# PowerSupply.net
KiCad netlist of a schematic drawn in Altium Designer
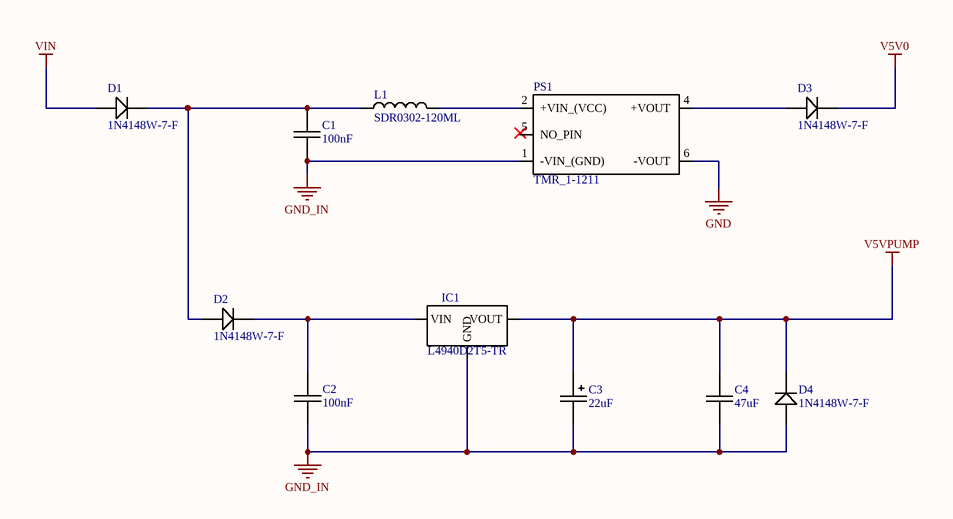
[diagram p0: PowerSupply.SchDoc]

(export (version "E")
  (design (tool "Eeschema 10.0.6"))
  (components
    (comp (ref "C1")
      (value "100nF")
      (footprint "SMD-CAP_1206_IPC_M")
      (description "Capacitor")
      (fields
        (field (name "MOUSER2 PART NUMBER") "80-C1206C104J3J")
        (field (name "MANUFACTURER_PART_NUMBER") "C1206C104J3JACTU")
      )
      (libsource (lib "JMD_Parts") (part "CAP-100NF-1206-5%-25V"))
    )
    (comp (ref "C2")
      (value "100nF")
      (footprint "SMD-CAP_1206_IPC_M")
      (description "Capacitor")
      (fields
        (field (name "MOUSER2 PART NUMBER") "80-C1206C104J3J")
        (field (name "MANUFACTURER_PART_NUMBER") "C1206C104J3JACTU")
      )
      (libsource (lib "JMD_Parts") (part "CAP-100NF-1206-5%-25V"))
    )
    (comp (ref "C3")
      (value "22uF")
      (footprint "CAPPM3216X180N")
      (description "Capacitor Polarised")
      (fields
        (field (name "MOUSER2 PART NUMBER") "581-TPSA226K010T0900")
        (field (name "MANUFACTURER_PART_NUMBER") "TPSA226K010T0900")
      )
      (libsource (lib "JMD_Parts") (part "CAP-22uF-Tantal-10%-10V"))
    )
    (comp (ref "C4")
      (value "47uF")
      (footprint "CAPC3216X180N")
      (description "Capacitor")
      (fields
        (field (name "MOUSER2 PART NUMBER") "80-C1206C476M8P")
        (field (name "MANUFACTURER_PART_NUMBER") "C1206C476M8PACTU")
      )
      (libsource (lib "JMD_Parts") (part "CAP-47UF-1206-20%-10V"))
    )
    (comp (ref "D1")
      (value "1N4148W-7-F")
      (footprint "SOD3716X115N")
      (description "Diode")
      (fields (field (name "MOUSER2 PART NUMBER") "621-1N4148W-F"))
      (libsource (lib "JMD_Parts") (part "1N4148W-7-F"))
    )
    (comp (ref "D2")
      (value "1N4148W-7-F")
      (footprint "SOD3716X115N")
      (description "Diode")
      (fields (field (name "MOUSER2 PART NUMBER") "621-1N4148W-F"))
      (libsource (lib "JMD_Parts") (part "1N4148W-7-F"))
    )
    (comp (ref "D3")
      (value "1N4148W-7-F")
      (footprint "SOD3716X115N")
      (description "Diode")
      (fields (field (name "MOUSER2 PART NUMBER") "621-1N4148W-F"))
      (libsource (lib "JMD_Parts") (part "1N4148W-7-F"))
    )
    (comp (ref "D4")
      (value "1N4148W-7-F")
      (footprint "SOD3716X115N")
      (description "Diode")
      (fields (field (name "MOUSER2 PART NUMBER") "621-1N4148W-F"))
      (libsource (lib "JMD_Parts") (part "1N4148W-7-F"))
    )
    (comp (ref "IC1")
      (value "L4940D2T5-TR")
      (footprint "ST_D2PAK")
      (description "Integrated Circuit")
      (libsource (lib "JMD_Parts") (part "L4940D2T5-TR"))
    )
    (comp (ref "L1")
      (value "SDR0302-120ML")
      (footprint "SDR0302-471KL")
      (description "Inductor")
      (fields (field (name "MOUSER2 PART NUMBER") "652-SDR0302-120ML"))
      (libsource (lib "JMD_Parts") (part "SDR0302-120ML"))
    )
    (comp (ref "PS1")
      (value "TMR_1-1211")
      (footprint "TMR-1-1215")
      (description "Power Supply")
      (fields
        (field (name "MOUSER2 PART NUMBER") "495-TMR-1-1211")
        (field (name "MANUFACTURER_PART_NUMBER") "TMR 1-1211")
      )
      (libsource (lib "JMD_Parts") (part "TMR_1-1211"))
    )
  )
  (nets
    (net (code "1") (name "GND") (class "Default")
      (node (ref "PS1") (pin "6") (pinfunction "-VOUT_6") (pintype "passive"))
    )
    (net (code "2") (name "GND_IN") (class "Default")
      (node (ref "C1") (pin "1") (pinfunction "1_1") (pintype "passive"))
      (node (ref "C2") (pin "1") (pinfunction "1_1") (pintype "passive"))
      (node (ref "C3") (pin "2") (pinfunction "2_2") (pintype "passive"))
      (node (ref "C4") (pin "1") (pinfunction "1_1") (pintype "passive"))
      (node (ref "D4") (pin "2") (pinfunction "A_2") (pintype "passive"))
      (node (ref "IC1") (pin "3") (pinfunction "GND_3") (pintype "passive"))
      (node (ref "PS1") (pin "1") (pinfunction "-VIN_(GND)_1") (pintype "passive"))
    )
    (net (code "3") (name "Net-(D1-K)") (class "Default")
      (node (ref "C1") (pin "2") (pinfunction "2_2") (pintype "passive"))
      (node (ref "D1") (pin "1") (pinfunction "K_1") (pintype "passive"))
      (node (ref "D2") (pin "2") (pinfunction "A_2") (pintype "passive"))
      (node (ref "L1") (pin "1") (pintype "passive"))
    )
    (net (code "4") (name "Net-(D2-K)") (class "Default")
      (node (ref "C2") (pin "2") (pinfunction "2_2") (pintype "passive"))
      (node (ref "D2") (pin "1") (pinfunction "K_1") (pintype "passive"))
      (node (ref "IC1") (pin "1") (pinfunction "VIN_1") (pintype "passive"))
    )
    (net (code "5") (name "Net-(D3-A)") (class "Default")
      (node (ref "D3") (pin "2") (pinfunction "A_2") (pintype "passive"))
      (node (ref "PS1") (pin "4") (pinfunction "+VOUT_4") (pintype "passive"))
    )
    (net (code "6") (name "Net-(PS1-+VIN_(VCC))") (class "Default")
      (node (ref "L1") (pin "2") (pintype "passive"))
      (node (ref "PS1") (pin "2") (pinfunction "+VIN_(VCC)_2") (pintype "passive"))
    )
    (net (code "7") (name "V5V0") (class "Default")
      (node (ref "D3") (pin "1") (pinfunction "K_1") (pintype "passive"))
    )
    (net (code "8") (name "V5VPUMP") (class "Default")
      (node (ref "C3") (pin "1") (pinfunction "1_1") (pintype "passive"))
      (node (ref "C4") (pin "2") (pinfunction "2_2") (pintype "passive"))
      (node (ref "D4") (pin "1") (pinfunction "K_1") (pintype "passive"))
      (node (ref "IC1") (pin "2") (pinfunction "VOUT_2") (pintype "passive"))
    )
    (net (code "9") (name "VIN") (class "Default")
      (node (ref "D1") (pin "2") (pinfunction "A_2") (pintype "passive"))
    )
    (net (code "10") (name "unconnected-(PS1-NO_PIN-Pad5)") (class "Default")
      (node (ref "PS1") (pin "5") (pinfunction "NO_PIN_5") (pintype "passive"))
    )
  )
)
